# Debug.net
KiCad netlist of a schematic drawn in EAGLE
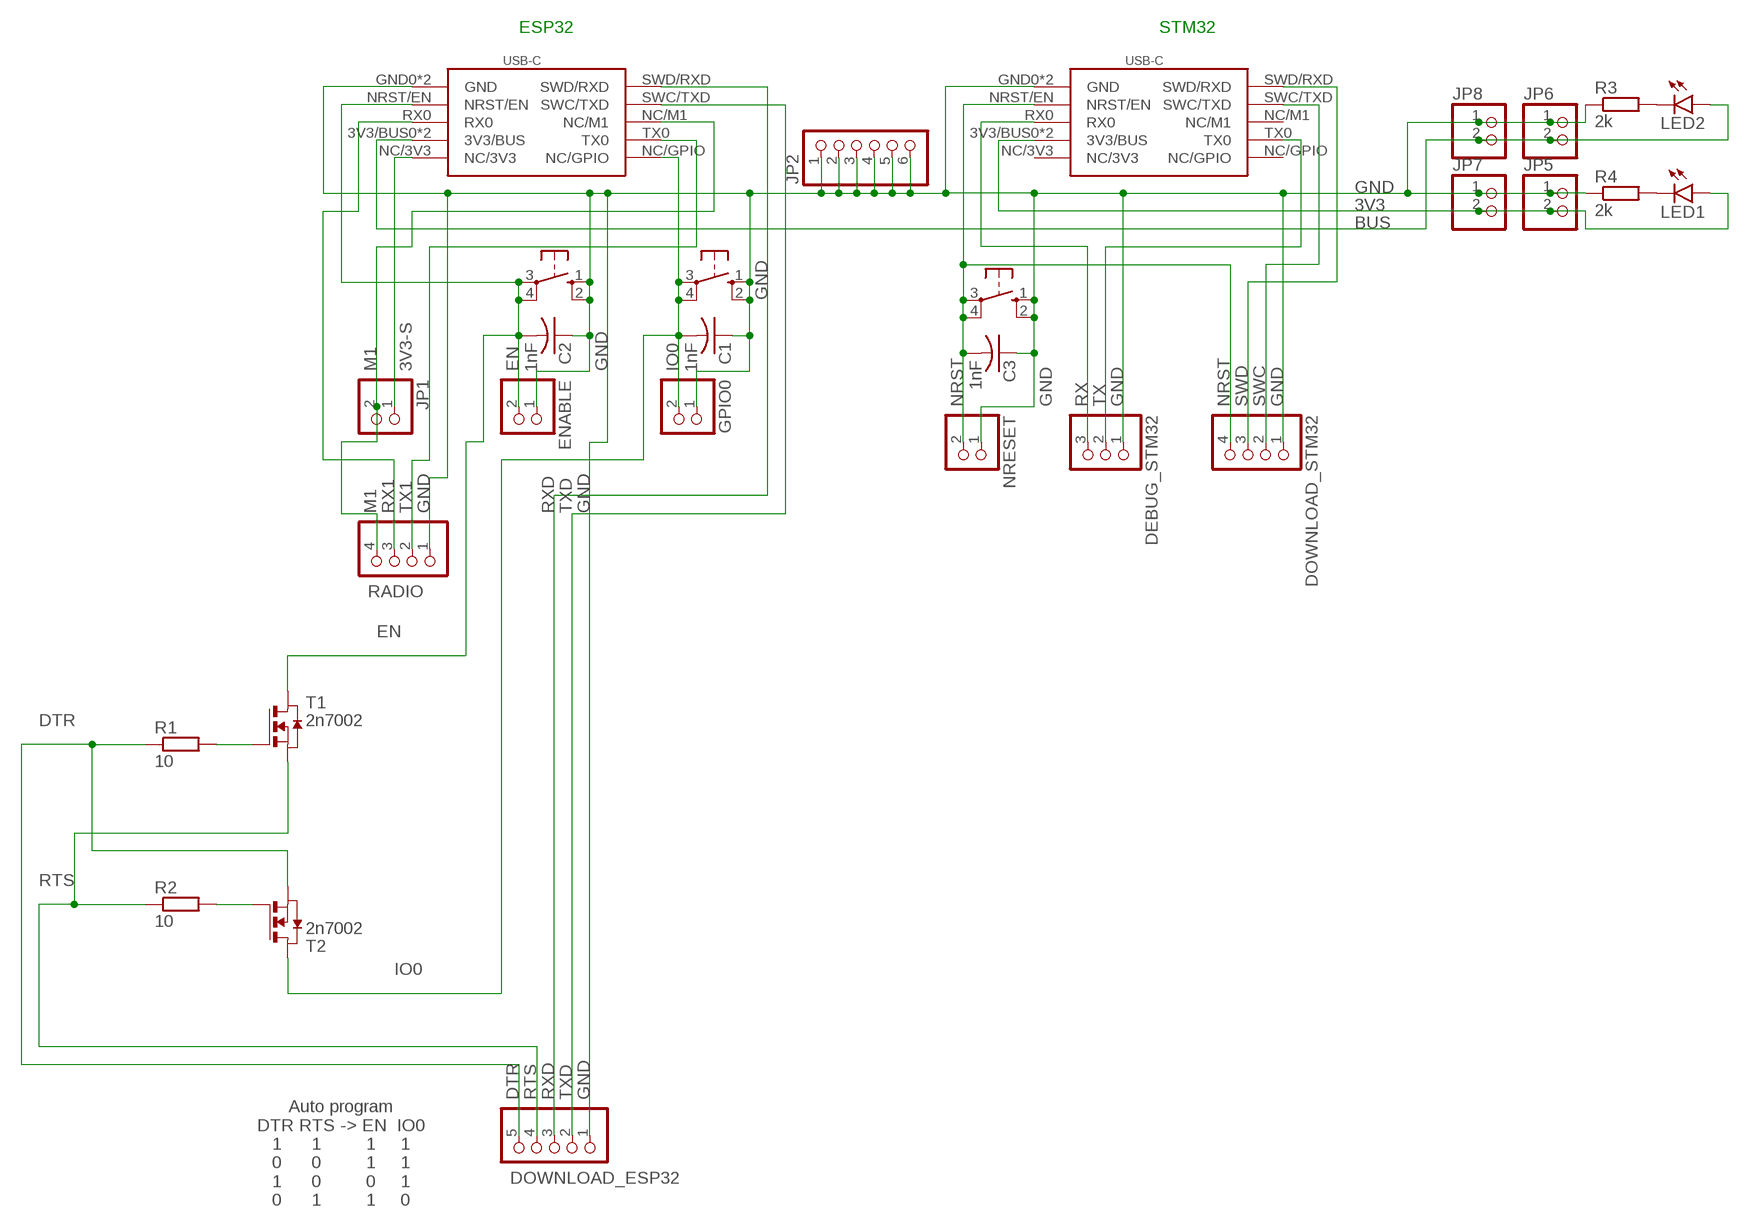
[diagram p0: schematic, sheet 1]

(export (version "E")
  (design (tool "Eeschema 10.0.6"))
  (components
    (comp (ref "C1")
      (value "1nF")
      (footprint "eagle-import:C0603")
      (libsource (lib "eagle-import") (part "C-USC0603"))
    )
    (comp (ref "C2")
      (value "1nF")
      (footprint "eagle-import:C0603")
      (libsource (lib "eagle-import") (part "C-USC0603"))
    )
    (comp (ref "C3")
      (value "1nF")
      (footprint "eagle-import:C0603")
      (libsource (lib "eagle-import") (part "C-USC0603"))
    )
    (comp (ref "DEBUG_STM32")
      (value "PINHD-1X3")
      (footprint "eagle-import:1X03")
      (libsource (lib "eagle-import") (part "PINHD-1X3"))
    )
    (comp (ref "DOWNLOAD_ESP32")
      (value "PINHD-1X5")
      (footprint "eagle-import:1X05")
      (libsource (lib "eagle-import") (part "PINHD-1X5"))
    )
    (comp (ref "DOWNLOAD_STM32")
      (value "PINHD-1X4")
      (footprint "eagle-import:1X04")
      (libsource (lib "eagle-import") (part "PINHD-1X4"))
    )
    (comp (ref "EN")
      (value "10-XX")
      (footprint "eagle-import:B3F-10XX")
      (fields (field (name "MPN") "B3F-1000"))
      (libsource (lib "eagle-import") (part "10-XX"))
    )
    (comp (ref "ENABLE")
      (value "PINHD-1X2")
      (footprint "eagle-import:1X02")
      (libsource (lib "eagle-import") (part "PINHD-1X2"))
    )
    (comp (ref "GPIO0")
      (value "PINHD-1X2")
      (footprint "eagle-import:1X02")
      (libsource (lib "eagle-import") (part "PINHD-1X2"))
    )
    (comp (ref "IO0")
      (value "10-XX")
      (footprint "eagle-import:B3F-10XX")
      (fields (field (name "MPN") "B3F-1000"))
      (libsource (lib "eagle-import") (part "10-XX"))
    )
    (comp (ref "JP1")
      (value "PINHD-1X2")
      (footprint "eagle-import:1X02")
      (libsource (lib "eagle-import") (part "PINHD-1X2"))
    )
    (comp (ref "JP2")
      (value "PINHD-1X6")
      (footprint "eagle-import:1X06")
      (libsource (lib "eagle-import") (part "PINHD-1X6"))
    )
    (comp (ref "JP5")
      (value "PINHD-1X2")
      (footprint "eagle-import:1X02")
      (libsource (lib "eagle-import") (part "PINHD-1X2"))
    )
    (comp (ref "JP6")
      (value "PINHD-1X2")
      (footprint "eagle-import:1X02")
      (libsource (lib "eagle-import") (part "PINHD-1X2"))
    )
    (comp (ref "JP7")
      (value "PINHD-1X2")
      (footprint "eagle-import:1X02")
      (libsource (lib "eagle-import") (part "PINHD-1X2"))
    )
    (comp (ref "JP8")
      (value "PINHD-1X2")
      (footprint "eagle-import:1X02")
      (libsource (lib "eagle-import") (part "PINHD-1X2"))
    )
    (comp (ref "LED1")
      (value "LEDCHIPLED_0603")
      (footprint "eagle-import:CHIPLED_0603")
      (libsource (lib "eagle-import") (part "LEDCHIPLED_0603"))
    )
    (comp (ref "LED2")
      (value "LEDCHIPLED_0603")
      (footprint "eagle-import:CHIPLED_0603")
      (libsource (lib "eagle-import") (part "LEDCHIPLED_0603"))
    )
    (comp (ref "NRESET")
      (value "PINHD-1X2")
      (footprint "eagle-import:1X02")
      (libsource (lib "eagle-import") (part "PINHD-1X2"))
    )
    (comp (ref "NRST")
      (value "10-XX")
      (footprint "eagle-import:B3F-10XX")
      (fields (field (name "MPN") "B3F-1000"))
      (libsource (lib "eagle-import") (part "10-XX"))
    )
    (comp (ref "R1")
      (value "10")
      (footprint "eagle-import:R0603")
      (libsource (lib "eagle-import") (part "R-EU_R0603"))
    )
    (comp (ref "R2")
      (value "10")
      (footprint "eagle-import:R0603")
      (libsource (lib "eagle-import") (part "R-EU_R0603"))
    )
    (comp (ref "R3")
      (value "2k")
      (footprint "eagle-import:R0603")
      (libsource (lib "eagle-import") (part "R-EU_R0603"))
    )
    (comp (ref "R4")
      (value "2k")
      (footprint "eagle-import:R0603")
      (libsource (lib "eagle-import") (part "R-EU_R0603"))
    )
    (comp (ref "RADIO")
      (value "PINHD-1X4")
      (footprint "eagle-import:1X04")
      (libsource (lib "eagle-import") (part "PINHD-1X4"))
    )
    (comp (ref "T1")
      (value "2n7002")
      (footprint "eagle-import:SOT-23")
      (libsource (lib "eagle-import") (part "NMOSSOT23"))
    )
    (comp (ref "T2")
      (value "2n7002")
      (footprint "eagle-import:SOT-23")
      (libsource (lib "eagle-import") (part "NMOSSOT23"))
    )
    (comp (ref "U$1")
      (value "USB-C")
      (footprint "eagle-import:USB-C")
      (libsource (lib "eagle-import") (part "USB-C"))
    )
    (comp (ref "U$2")
      (value "USB-C")
      (footprint "eagle-import:USB-C")
      (libsource (lib "eagle-import") (part "USB-C"))
    )
  )
  (nets
    (net (code "1") (name "/3V3") (class "Default")
      (node (ref "JP5") (pin "2") (pinfunction "2_2") (pintype "passive"))
      (node (ref "JP7") (pin "2") (pinfunction "2_2") (pintype "passive"))
      (node (ref "LED1") (pin "A") (pinfunction "A_A") (pintype "passive"))
      (node (ref "U$2") (pin "3V3/BUS0") (pinfunction "3V3/BUS_3V3/BUS0") (pintype "bidirectional"))
      (node (ref "U$2") (pin "3V3/BUS1") (pinfunction "3V3/BUS_3V3/BUS1") (pintype "bidirectional"))
    )
    (net (code "2") (name "/3V3-S") (class "Default")
      (node (ref "JP1") (pin "1") (pinfunction "1_1") (pintype "passive"))
      (node (ref "U$1") (pin "NC/3V3") (pinfunction "NC/3V3_NC/3V3") (pintype "bidirectional"))
    )
    (net (code "3") (name "/BUS") (class "Default")
      (node (ref "JP6") (pin "2") (pinfunction "2_2") (pintype "passive"))
      (node (ref "JP8") (pin "2") (pinfunction "2_2") (pintype "passive"))
      (node (ref "LED2") (pin "A") (pinfunction "A_A") (pintype "passive"))
      (node (ref "U$1") (pin "3V3/BUS0") (pinfunction "3V3/BUS_3V3/BUS0") (pintype "bidirectional"))
      (node (ref "U$1") (pin "3V3/BUS1") (pinfunction "3V3/BUS_3V3/BUS1") (pintype "bidirectional"))
    )
    (net (code "4") (name "/DTR") (class "Default")
      (node (ref "DOWNLOAD_ESP32") (pin "5") (pinfunction "5_5") (pintype "passive"))
      (node (ref "R1") (pin "1") (pinfunction "1_1") (pintype "passive"))
      (node (ref "T2") (pin "2") (pinfunction "S_2") (pintype "passive"))
    )
    (net (code "5") (name "/EN") (class "Default")
      (node (ref "C2") (pin "2") (pinfunction "2_2") (pintype "passive"))
      (node (ref "EN") (pin "3") (pinfunction "P_3") (pintype "passive"))
      (node (ref "EN") (pin "4") (pinfunction "P1_4") (pintype "passive"))
      (node (ref "ENABLE") (pin "2") (pinfunction "2_2") (pintype "passive"))
      (node (ref "T1") (pin "1") (pinfunction "D_1") (pintype "passive"))
      (node (ref "U$1") (pin "NRST/EN") (pinfunction "NRST/EN_NRST/EN") (pintype "bidirectional"))
    )
    (net (code "6") (name "/GND") (class "Default")
      (node (ref "C1") (pin "1") (pinfunction "1_1") (pintype "passive"))
      (node (ref "C2") (pin "1") (pinfunction "1_1") (pintype "passive"))
      (node (ref "C3") (pin "1") (pinfunction "1_1") (pintype "passive"))
      (node (ref "DEBUG_STM32") (pin "1") (pinfunction "1_1") (pintype "passive"))
      (node (ref "DOWNLOAD_ESP32") (pin "1") (pinfunction "1_1") (pintype "passive"))
      (node (ref "DOWNLOAD_STM32") (pin "1") (pinfunction "1_1") (pintype "passive"))
      (node (ref "EN") (pin "1") (pinfunction "S_1") (pintype "passive"))
      (node (ref "EN") (pin "2") (pinfunction "S1_2") (pintype "passive"))
      (node (ref "ENABLE") (pin "1") (pinfunction "1_1") (pintype "passive"))
      (node (ref "GPIO0") (pin "1") (pinfunction "1_1") (pintype "passive"))
      (node (ref "IO0") (pin "1") (pinfunction "S_1") (pintype "passive"))
      (node (ref "IO0") (pin "2") (pinfunction "S1_2") (pintype "passive"))
      (node (ref "JP2") (pin "1") (pinfunction "1_1") (pintype "passive"))
      (node (ref "JP2") (pin "2") (pinfunction "2_2") (pintype "passive"))
      (node (ref "JP2") (pin "3") (pinfunction "3_3") (pintype "passive"))
      (node (ref "JP2") (pin "4") (pinfunction "4_4") (pintype "passive"))
      (node (ref "JP2") (pin "5") (pinfunction "5_5") (pintype "passive"))
      (node (ref "JP2") (pin "6") (pinfunction "6_6") (pintype "passive"))
      (node (ref "JP5") (pin "1") (pinfunction "1_1") (pintype "passive"))
      (node (ref "JP6") (pin "1") (pinfunction "1_1") (pintype "passive"))
      (node (ref "JP7") (pin "1") (pinfunction "1_1") (pintype "passive"))
      (node (ref "JP8") (pin "1") (pinfunction "1_1") (pintype "passive"))
      (node (ref "NRESET") (pin "1") (pinfunction "1_1") (pintype "passive"))
      (node (ref "NRST") (pin "1") (pinfunction "S_1") (pintype "passive"))
      (node (ref "NRST") (pin "2") (pinfunction "S1_2") (pintype "passive"))
      (node (ref "R3") (pin "1") (pinfunction "1_1") (pintype "passive"))
      (node (ref "R4") (pin "1") (pinfunction "1_1") (pintype "passive"))
      (node (ref "RADIO") (pin "1") (pinfunction "1_1") (pintype "passive"))
      (node (ref "U$1") (pin "GND0") (pinfunction "GND_GND0") (pintype "bidirectional"))
      (node (ref "U$1") (pin "GND1") (pinfunction "GND_GND1") (pintype "bidirectional"))
      (node (ref "U$2") (pin "GND0") (pinfunction "GND_GND0") (pintype "bidirectional"))
      (node (ref "U$2") (pin "GND1") (pinfunction "GND_GND1") (pintype "bidirectional"))
    )
    (net (code "7") (name "/IO0") (class "Default")
      (node (ref "C1") (pin "2") (pinfunction "2_2") (pintype "passive"))
      (node (ref "GPIO0") (pin "2") (pinfunction "2_2") (pintype "passive"))
      (node (ref "IO0") (pin "3") (pinfunction "P_3") (pintype "passive"))
      (node (ref "IO0") (pin "4") (pinfunction "P1_4") (pintype "passive"))
      (node (ref "T2") (pin "1") (pinfunction "D_1") (pintype "passive"))
      (node (ref "U$1") (pin "NC/GPIO") (pinfunction "NC/GPIO_NC/GPIO") (pintype "bidirectional"))
    )
    (net (code "8") (name "/M1") (class "Default")
      (node (ref "JP1") (pin "2") (pinfunction "2_2") (pintype "passive"))
      (node (ref "RADIO") (pin "4") (pinfunction "4_4") (pintype "passive"))
      (node (ref "U$1") (pin "NC/M1") (pinfunction "NC/M1_NC/M1") (pintype "bidirectional"))
    )
    (net (code "9") (name "/NRST") (class "Default")
      (node (ref "C3") (pin "2") (pinfunction "2_2") (pintype "passive"))
      (node (ref "DOWNLOAD_STM32") (pin "4") (pinfunction "4_4") (pintype "passive"))
      (node (ref "NRESET") (pin "2") (pinfunction "2_2") (pintype "passive"))
      (node (ref "NRST") (pin "3") (pinfunction "P_3") (pintype "passive"))
      (node (ref "NRST") (pin "4") (pinfunction "P1_4") (pintype "passive"))
      (node (ref "U$2") (pin "NRST/EN") (pinfunction "NRST/EN_NRST/EN") (pintype "bidirectional"))
    )
    (net (code "10") (name "/RTS") (class "Default")
      (node (ref "DOWNLOAD_ESP32") (pin "4") (pinfunction "4_4") (pintype "passive"))
      (node (ref "R2") (pin "1") (pinfunction "1_1") (pintype "passive"))
      (node (ref "T1") (pin "2") (pinfunction "S_2") (pintype "passive"))
    )
    (net (code "11") (name "/RX") (class "Default")
      (node (ref "DEBUG_STM32") (pin "3") (pinfunction "3_3") (pintype "passive"))
      (node (ref "U$2") (pin "RX0") (pinfunction "RX0_RX0") (pintype "bidirectional"))
    )
    (net (code "12") (name "/RX1") (class "Default")
      (node (ref "RADIO") (pin "3") (pinfunction "3_3") (pintype "passive"))
      (node (ref "U$1") (pin "RX0") (pinfunction "RX0_RX0") (pintype "bidirectional"))
    )
    (net (code "13") (name "/RXD") (class "Default")
      (node (ref "DOWNLOAD_ESP32") (pin "3") (pinfunction "3_3") (pintype "passive"))
      (node (ref "U$1") (pin "SWD/RXD") (pinfunction "SWD/RXD_SWD/RXD") (pintype "bidirectional"))
    )
    (net (code "14") (name "/SWC") (class "Default")
      (node (ref "DOWNLOAD_STM32") (pin "2") (pinfunction "2_2") (pintype "passive"))
      (node (ref "U$2") (pin "SWC/TXD") (pinfunction "SWC/TXD_SWC/TXD") (pintype "bidirectional"))
    )
    (net (code "15") (name "/SWD") (class "Default")
      (node (ref "DOWNLOAD_STM32") (pin "3") (pinfunction "3_3") (pintype "passive"))
      (node (ref "U$2") (pin "SWD/RXD") (pinfunction "SWD/RXD_SWD/RXD") (pintype "bidirectional"))
    )
    (net (code "16") (name "/TX") (class "Default")
      (node (ref "DEBUG_STM32") (pin "2") (pinfunction "2_2") (pintype "passive"))
      (node (ref "U$2") (pin "TX0") (pinfunction "TX0_TX0") (pintype "bidirectional"))
    )
    (net (code "17") (name "/TX1") (class "Default")
      (node (ref "RADIO") (pin "2") (pinfunction "2_2") (pintype "passive"))
      (node (ref "U$1") (pin "TX0") (pinfunction "TX0_TX0") (pintype "bidirectional"))
    )
    (net (code "18") (name "/TXD") (class "Default")
      (node (ref "DOWNLOAD_ESP32") (pin "2") (pinfunction "2_2") (pintype "passive"))
      (node (ref "U$1") (pin "SWC/TXD") (pinfunction "SWC/TXD_SWC/TXD") (pintype "bidirectional"))
    )
    (net (code "19") (name "Net-(LED1-PadC)") (class "Default")
      (node (ref "LED1") (pin "C") (pinfunction "C_C") (pintype "passive"))
      (node (ref "R4") (pin "2") (pinfunction "2_2") (pintype "passive"))
    )
    (net (code "20") (name "Net-(LED2-PadC)") (class "Default")
      (node (ref "LED2") (pin "C") (pinfunction "C_C") (pintype "passive"))
      (node (ref "R3") (pin "2") (pinfunction "2_2") (pintype "passive"))
    )
    (net (code "21") (name "Net-(T1-G)") (class "Default")
      (node (ref "R1") (pin "2") (pinfunction "2_2") (pintype "passive"))
      (node (ref "T1") (pin "3") (pinfunction "G_3") (pintype "passive"))
    )
    (net (code "22") (name "Net-(T2-G)") (class "Default")
      (node (ref "R2") (pin "2") (pinfunction "2_2") (pintype "passive"))
      (node (ref "T2") (pin "3") (pinfunction "G_3") (pintype "passive"))
    )
    (net (code "23") (name "unconnected-(U$2-PadNC{slash}3V3)") (class "Default")
      (node (ref "U$2") (pin "NC/3V3") (pinfunction "NC/3V3_NC/3V3") (pintype "bidirectional"))
    )
    (net (code "24") (name "unconnected-(U$2-PadNC{slash}GPIO)") (class "Default")
      (node (ref "U$2") (pin "NC/GPIO") (pinfunction "NC/GPIO_NC/GPIO") (pintype "bidirectional"))
    )
    (net (code "25") (name "unconnected-(U$2-PadNC{slash}M1)") (class "Default")
      (node (ref "U$2") (pin "NC/M1") (pinfunction "NC/M1_NC/M1") (pintype "bidirectional"))
    )
  )
)
